# V1_0.net
KiCad netlist of a schematic drawn in Altium Designer
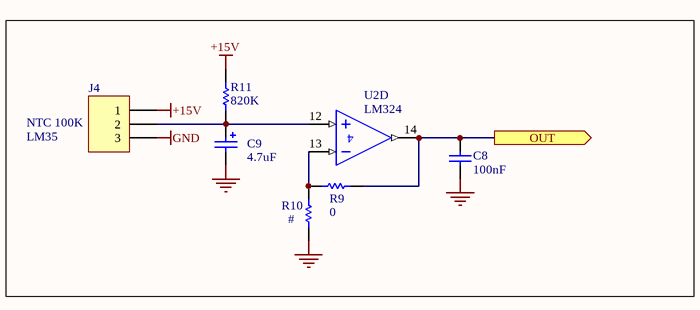
[diagram p0: V1.0.SchDoc]

(export (version "E")
  (design (tool "Eeschema 10.0.6"))
  (components
    (comp (ref "C8")
      (value "100nF")
      (footprint "CAPNTO2.54-3.05x1.78A")
      (description "Capacitor")
      (fields (field (name "MANUFACTURER") "Generic Components") (field (name "PUBLISHER") "Altium Limited"))
      (libsource (lib "Miscellaneous Devices") (part "Cap"))
    )
    (comp (ref "C9")
      (value "4.7uF")
      (footprint "CAPPR2.5-6.3x5")
      (description "Polarized Capacitor (Radial)")
      (fields (field (name "MANUFACTURER") "Generic Components") (field (name "PUBLISHER") "Altium Limited"))
      (libsource (lib "Miscellaneous Devices") (part "Cap Pol1"))
    )
    (comp (ref "J4")
      (value "3PIN")
      (footprint "Fonics_3PIN_1")
      (description "Header, 3-Pin")
      (fields (field (name "MANUFACTURER") "Generic Components") (field (name "PUBLISHER") "Altium Limited"))
      (libsource (lib "Miscellaneous Connectors") (part "Header 3"))
    )
    (comp (ref "R9")
      (value "0")
      (footprint "AXIAL-0.4")
      (description "Resistor")
      (fields (field (name "PUBLISHER") "Altium Limited"))
      (libsource (lib "Miscellaneous Devices") (part "Res1"))
    )
    (comp (ref "R10")
      (value "#")
      (footprint "AXIAL-0.4")
      (description "Resistor")
      (fields (field (name "PUBLISHER") "Altium Limited"))
      (libsource (lib "Miscellaneous Devices") (part "Res1"))
    )
    (comp (ref "R11")
      (value "820K")
      (footprint "AXIAL-0.4")
      (description "Resistor")
      (fields (field (name "PUBLISHER") "Altium Limited"))
      (libsource (lib "Miscellaneous Devices") (part "Res1"))
    )
    (comp (ref "U2")
      (value "LM324")
      (footprint "646-06")
      (description "Quad Low-Power Operational Amplifier")
      (fields (field (name "PUBLISHER") "Altium Limited"))
      (libsource (lib "my Libraries") (part "LM324"))
    )
  )
  (nets
    (net (code "1") (name "+15V") (class "Default")
      (node (ref "J4") (pin "1") (pinfunction "1_1") (pintype "passive"))
      (node (ref "R11") (pin "1") (pinfunction "1_1") (pintype "passive"))
    )
    (net (code "2") (name "/OUT") (class "Default")
      (node (ref "C8") (pin "2") (pinfunction "2_2") (pintype "passive"))
      (node (ref "R9") (pin "1") (pinfunction "1_1") (pintype "passive"))
      (node (ref "U2") (pin "14") (pinfunction "OUT_14") (pintype "output"))
    )
    (net (code "3") (name "GND") (class "Default")
      (node (ref "C8") (pin "1") (pinfunction "1_1") (pintype "passive"))
      (node (ref "C9") (pin "2") (pinfunction "2_2") (pintype "passive"))
      (node (ref "J4") (pin "3") (pinfunction "3_3") (pintype "passive"))
      (node (ref "R10") (pin "2") (pinfunction "2_2") (pintype "passive"))
    )
    (net (code "4") (name "Net-(U2D-IN+)") (class "Default")
      (node (ref "C9") (pin "1") (pinfunction "1_1") (pintype "passive"))
      (node (ref "J4") (pin "2") (pinfunction "2_2") (pintype "passive"))
      (node (ref "R11") (pin "2") (pinfunction "2_2") (pintype "passive"))
      (node (ref "U2") (pin "12") (pinfunction "IN+_12") (pintype "input"))
    )
    (net (code "5") (name "Net-(U2D-IN-)") (class "Default")
      (node (ref "R10") (pin "1") (pinfunction "1_1") (pintype "passive"))
      (node (ref "R9") (pin "2") (pinfunction "2_2") (pintype "passive"))
      (node (ref "U2") (pin "13") (pinfunction "IN-_13") (pintype "input"))
    )
  )
)
